# ACinputSide.net
KiCad netlist of a schematic drawn in EAGLE
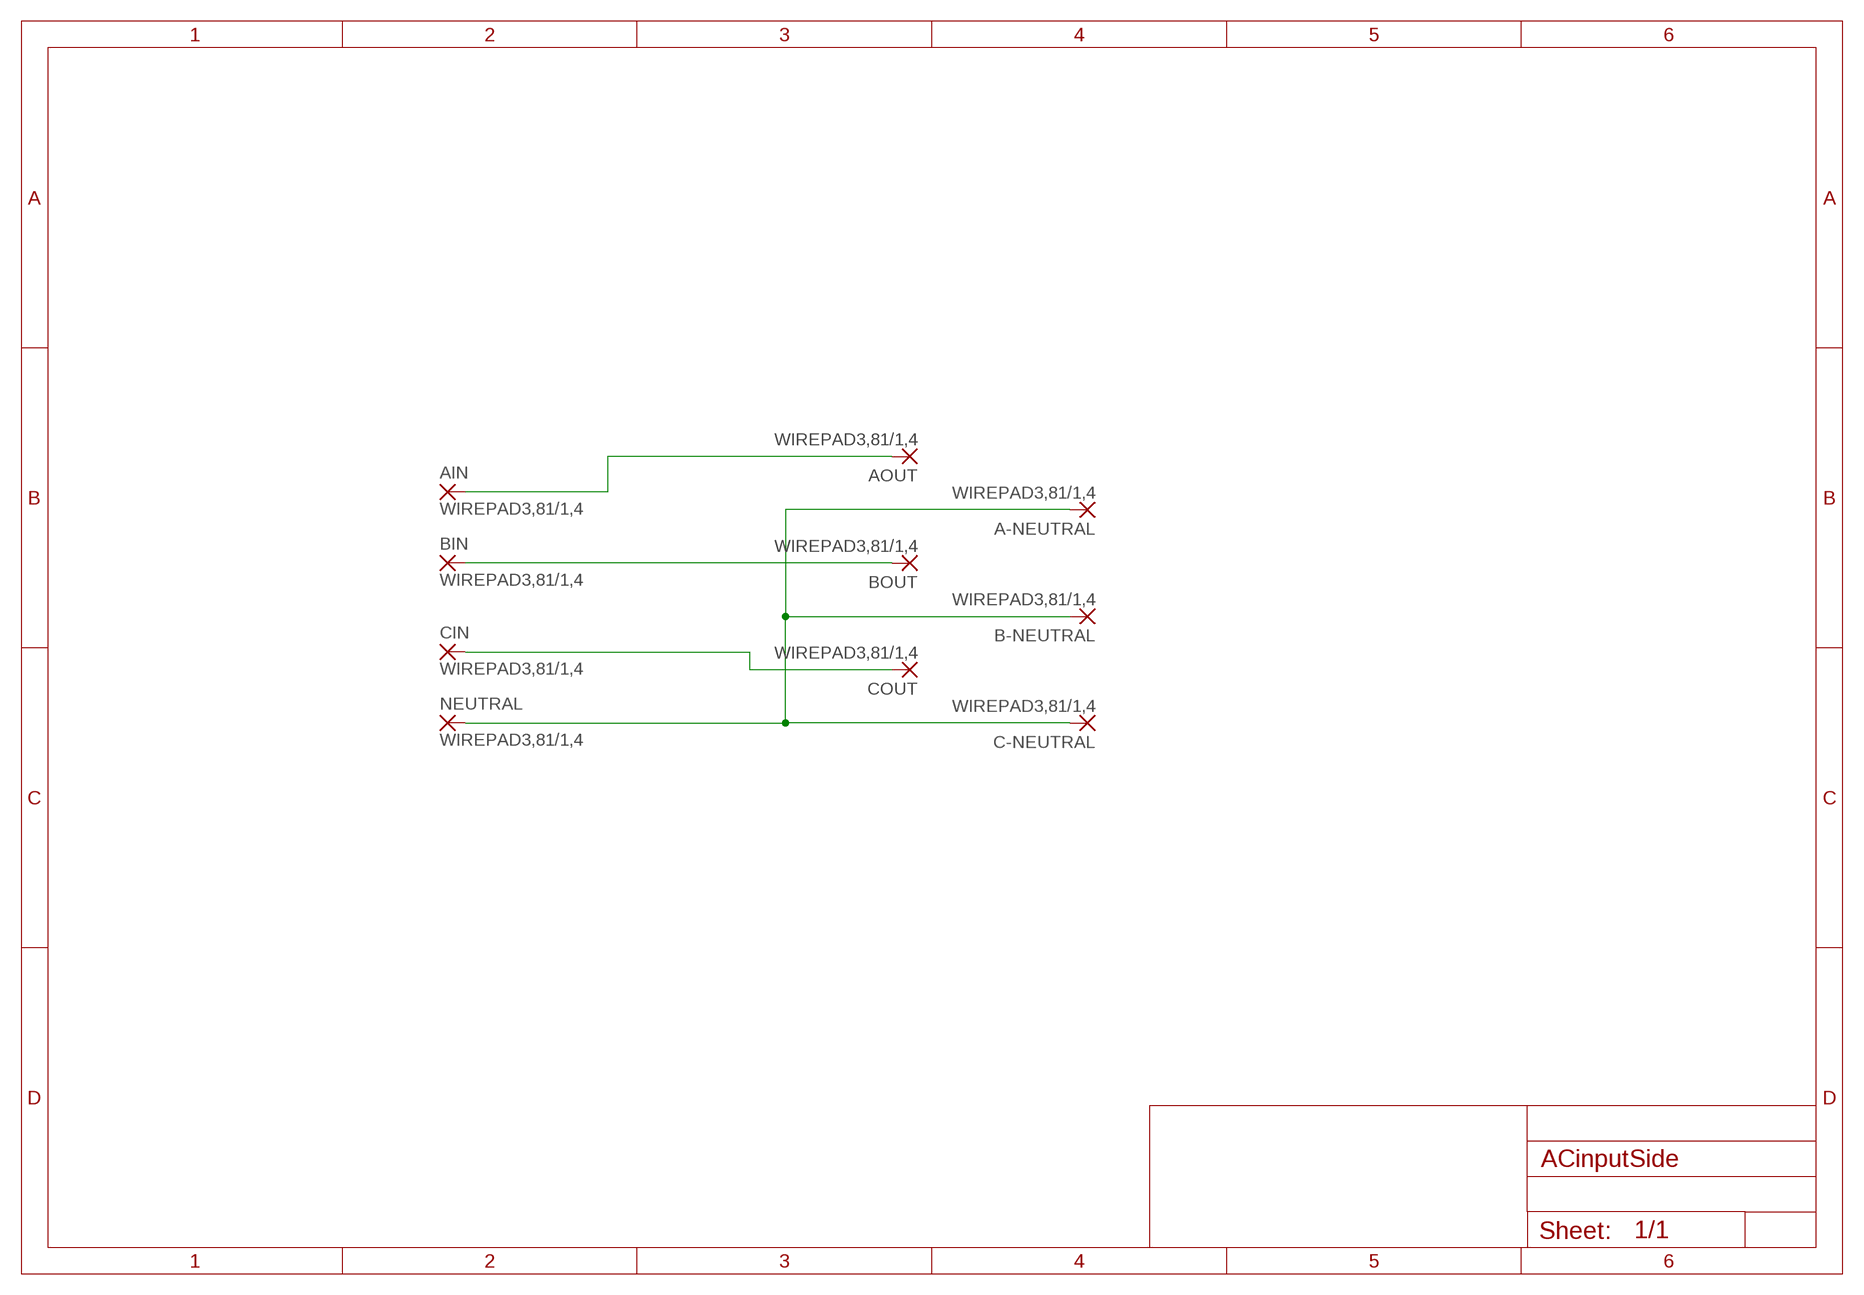
[diagram p0: schematic, sheet 1]

(export (version "E")
  (design (tool "Eeschema 10.0.6"))
  (components
    (comp (ref "A-NEUTRAL")
      (value "WIREPAD3,81/1,4")
      (footprint "eagle-import:3,81_1,4")
      (libsource (lib "eagle-import") (part "WIREPAD3,81/1,4"))
    )
    (comp (ref "AIN")
      (value "WIREPAD3,81/1,4")
      (footprint "eagle-import:3,81_1,4")
      (libsource (lib "eagle-import") (part "WIREPAD3,81/1,4"))
    )
    (comp (ref "AOUT")
      (value "WIREPAD3,81/1,4")
      (footprint "eagle-import:3,81_1,4")
      (libsource (lib "eagle-import") (part "WIREPAD3,81/1,4"))
    )
    (comp (ref "B-NEUTRAL")
      (value "WIREPAD3,81/1,4")
      (footprint "eagle-import:3,81_1,4")
      (libsource (lib "eagle-import") (part "WIREPAD3,81/1,4"))
    )
    (comp (ref "BIN")
      (value "WIREPAD3,81/1,4")
      (footprint "eagle-import:3,81_1,4")
      (libsource (lib "eagle-import") (part "WIREPAD3,81/1,4"))
    )
    (comp (ref "BOUT")
      (value "WIREPAD3,81/1,4")
      (footprint "eagle-import:3,81_1,4")
      (libsource (lib "eagle-import") (part "WIREPAD3,81/1,4"))
    )
    (comp (ref "C-NEUTRAL")
      (value "WIREPAD3,81/1,4")
      (footprint "eagle-import:3,81_1,4")
      (libsource (lib "eagle-import") (part "WIREPAD3,81/1,4"))
    )
    (comp (ref "CIN")
      (value "WIREPAD3,81/1,4")
      (footprint "eagle-import:3,81_1,4")
      (libsource (lib "eagle-import") (part "WIREPAD3,81/1,4"))
    )
    (comp (ref "COUT")
      (value "WIREPAD3,81/1,4")
      (footprint "eagle-import:3,81_1,4")
      (libsource (lib "eagle-import") (part "WIREPAD3,81/1,4"))
    )
    (comp (ref "NEUTRAL")
      (value "WIREPAD3,81/1,4")
      (footprint "eagle-import:3,81_1,4")
      (libsource (lib "eagle-import") (part "WIREPAD3,81/1,4"))
    )
  )
  (nets
    (net (code "1") (name "Net-(A-NEUTRAL-P)") (class "Default")
      (node (ref "A-NEUTRAL") (pin "1") (pinfunction "P_1") (pintype "passive"))
      (node (ref "B-NEUTRAL") (pin "1") (pinfunction "P_1") (pintype "passive"))
      (node (ref "C-NEUTRAL") (pin "1") (pinfunction "P_1") (pintype "passive"))
      (node (ref "NEUTRAL") (pin "1") (pinfunction "P_1") (pintype "passive"))
    )
    (net (code "2") (name "Net-(AIN-P)") (class "Default")
      (node (ref "AIN") (pin "1") (pinfunction "P_1") (pintype "passive"))
      (node (ref "AOUT") (pin "1") (pinfunction "P_1") (pintype "passive"))
    )
    (net (code "3") (name "Net-(BIN-P)") (class "Default")
      (node (ref "BIN") (pin "1") (pinfunction "P_1") (pintype "passive"))
      (node (ref "BOUT") (pin "1") (pinfunction "P_1") (pintype "passive"))
    )
    (net (code "4") (name "Net-(CIN-P)") (class "Default")
      (node (ref "CIN") (pin "1") (pinfunction "P_1") (pintype "passive"))
      (node (ref "COUT") (pin "1") (pinfunction "P_1") (pintype "passive"))
    )
  )
)
